# MCU.net
KiCad netlist of a schematic drawn in Altium Designer
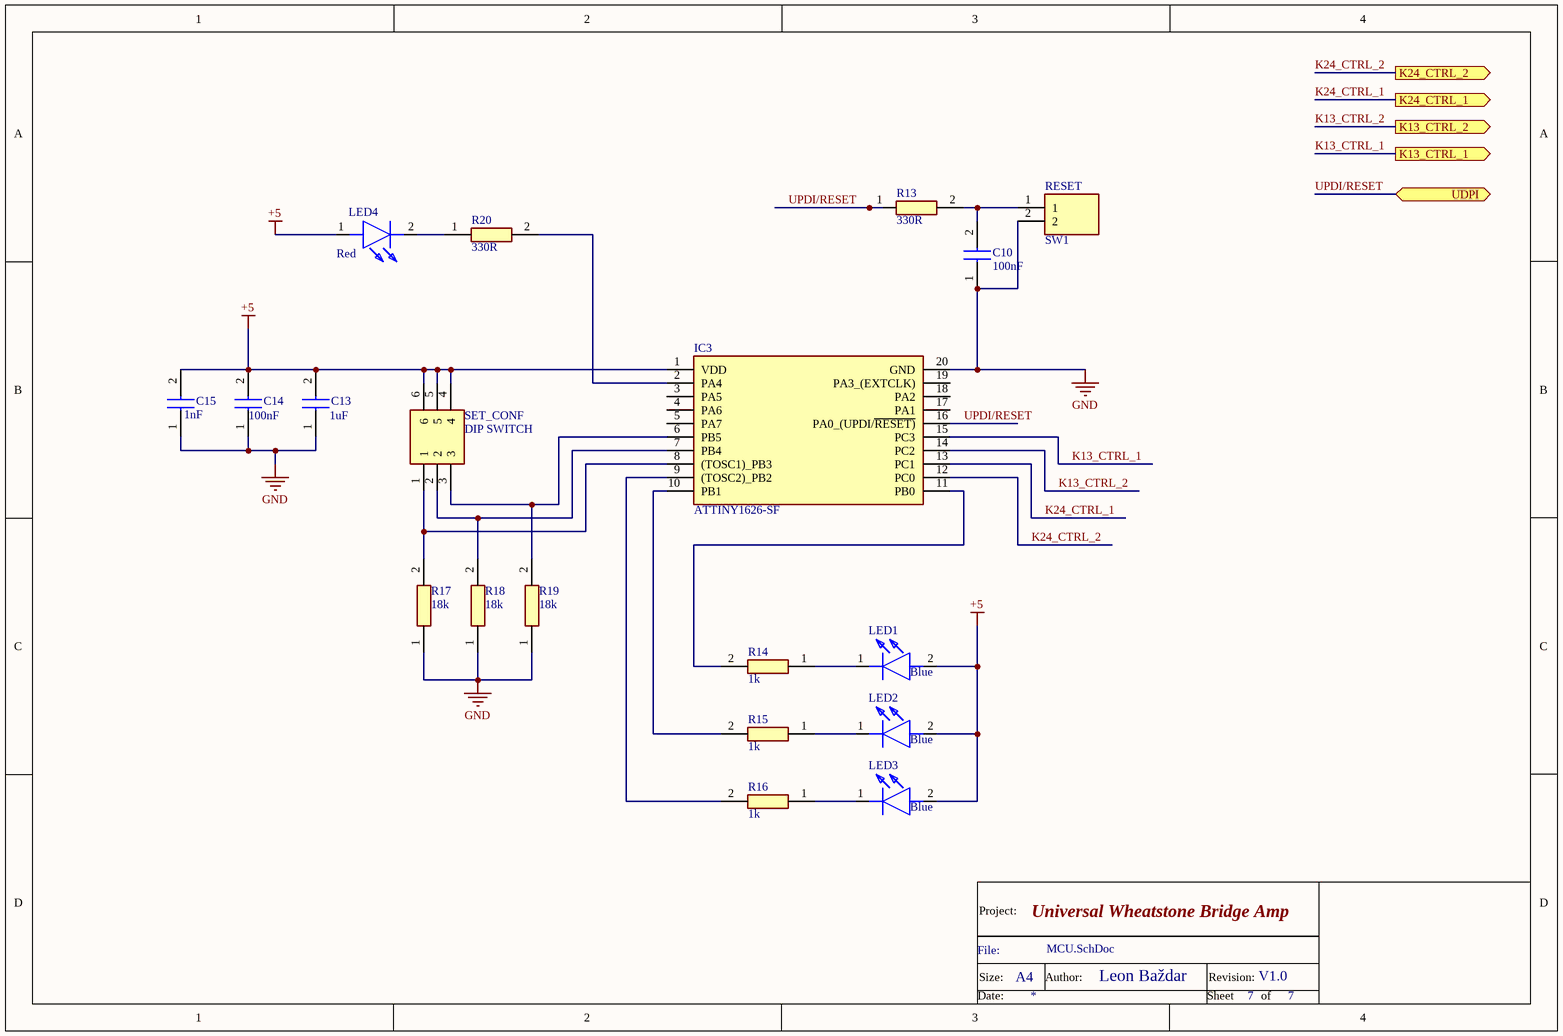
[diagram p0: MCU.SchDoc]

(export (version "E")
  (design (tool "Eeschema 10.0.6"))
  (components
    (comp (ref "C10")
      (value "100nF")
      (footprint "SamacSys:CAPC1005X55N")
      (description "Capacitor")
      (fields (field (name "MANUFACTURER_PART_NUMBER") "GCM155L81E104KE02D"))
      (libsource (lib "*") (part "GCM155L81E104KE02D"))
    )
    (comp (ref "C13")
      (value "1uF")
      (footprint "SamacSys:CAPC1005X55N")
      (description "Capacitor")
      (fields (field (name "MANUFACTURER_PART_NUMBER") "GRT155C81E105KE13D"))
      (libsource (lib "*") (part "GRT155C81E105KE13D"))
    )
    (comp (ref "C14")
      (value "100nF")
      (footprint "SamacSys:CAPC1005X55N")
      (description "Capacitor")
      (fields (field (name "MANUFACTURER_PART_NUMBER") "GCM155L81E104KE02D"))
      (libsource (lib "*") (part "GCM155L81E104KE02D"))
    )
    (comp (ref "C15")
      (value "1nF")
      (footprint "SamacSys:CAPC1005X55N")
      (description "Capacitor")
      (fields (field (name "MANUFACTURER_PART_NUMBER") "CGA2B2C0G1H102J050BE"))
      (libsource (lib "*") (part "CGA2B2C0G1H102J050BE"))
    )
    (comp (ref "IC3")
      (value "ATTINY1626-SF")
      (footprint "SamacSys:SOIC127P1030X265-20N")
      (description "Integrated Circuit")
      (libsource (lib "*") (part "ATTINY1626-SF"))
    )
    (comp (ref "LED1")
      (value "Blue")
      (footprint "SamacSys:LEDC2012X85N")
      (description "LED")
      (fields
        (field (name "MOUSER2 PART NUMBER") "604-APT2012LVBCD")
        (field (name "MANUFACTURER_PART_NUMBER") "APT2012LVBC/D")
      )
      (libsource (lib "*") (part "APT2012LVBC_D"))
    )
    (comp (ref "LED2")
      (value "Blue")
      (footprint "SamacSys:LEDC2012X85N")
      (description "LED")
      (fields
        (field (name "MOUSER2 PART NUMBER") "604-APT2012LVBCD")
        (field (name "MANUFACTURER_PART_NUMBER") "APT2012LVBC/D")
      )
      (libsource (lib "*") (part "APT2012LVBC_D"))
    )
    (comp (ref "LED3")
      (value "Blue")
      (footprint "SamacSys:LEDC2012X85N")
      (description "LED")
      (fields
        (field (name "MOUSER2 PART NUMBER") "604-APT2012LVBCD")
        (field (name "MANUFACTURER_PART_NUMBER") "APT2012LVBC/D")
      )
      (libsource (lib "*") (part "APT2012LVBC_D"))
    )
    (comp (ref "LED4")
      (value "Red")
      (footprint "SamacSys:APT2012SECKJ3PRV")
      (description "LED")
      (fields (field (name "MANUFACTURER_PART_NUMBER") "APT2012SECK/J3-PRV"))
      (libsource (lib "*") (part "APT2012SECK_J3-PRV"))
    )
    (comp (ref "R13")
      (value "330R")
      (footprint "SamacSys:ERJ2RKD1004X")
      (description "Resistor")
      (fields (field (name "MANUFACTURER_PART_NUMBER") "ERJ-2RHD3300X"))
      (libsource (lib "*") (part "ERJ-2RHD3300X"))
    )
    (comp (ref "R14")
      (value "1k")
      (footprint "SamacSys:ERA2V_(0402)")
      (description "Resistor")
      (fields (field (name "MANUFACTURER_PART_NUMBER") "ERA-2VEB1001X"))
      (libsource (lib "*") (part "ERA-2VEB1001X"))
    )
    (comp (ref "R15")
      (value "1k")
      (footprint "SamacSys:ERA2V_(0402)")
      (description "Resistor")
      (fields (field (name "MANUFACTURER_PART_NUMBER") "ERA-2VEB1001X"))
      (libsource (lib "*") (part "ERA-2VEB1001X"))
    )
    (comp (ref "R16")
      (value "1k")
      (footprint "SamacSys:ERA2V_(0402)")
      (description "Resistor")
      (fields (field (name "MANUFACTURER_PART_NUMBER") "ERA-2VEB1001X"))
      (libsource (lib "*") (part "ERA-2VEB1001X"))
    )
    (comp (ref "R17")
      (value "18k")
      (footprint "SamacSys:RESC1005X35N")
      (description "Resistor")
      (fields (field (name "MANUFACTURER_PART_NUMBER") "CPF0402B18KE1"))
      (libsource (lib "*") (part "CPF0402B18KE1"))
    )
    (comp (ref "R18")
      (value "18k")
      (footprint "SamacSys:RESC1005X35N")
      (description "Resistor")
      (fields (field (name "MANUFACTURER_PART_NUMBER") "CPF0402B18KE1"))
      (libsource (lib "*") (part "CPF0402B18KE1"))
    )
    (comp (ref "R19")
      (value "18k")
      (footprint "SamacSys:RESC1005X35N")
      (description "Resistor")
      (fields (field (name "MANUFACTURER_PART_NUMBER") "CPF0402B18KE1"))
      (libsource (lib "*") (part "CPF0402B18KE1"))
    )
    (comp (ref "R20")
      (value "330R")
      (footprint "SamacSys:ERJ2RKD1004X")
      (description "Resistor")
      (fields (field (name "MANUFACTURER_PART_NUMBER") "ERJ-2RHD3300X"))
      (libsource (lib "*") (part "ERJ-2RHD3300X"))
    )
    (comp (ref "RESET")
      (value "SW1")
      (footprint "SamacSys:95C04A3GWRT")
      (description "Switch")
      (fields
        (field (name "MOUSER2 PART NUMBER") "706-95C04A3GWRT")
        (field (name "MANUFACTURER_PART_NUMBER") "95C04A3GWRT")
      )
      (libsource (lib "*") (part "95C04A3GWRT"))
    )
    (comp (ref "SET_CONF")
      (value "DIP SWITCH")
      (footprint "SamacSys:2193LPSTR")
      (description "Switch")
      (fields (field (name "MANUFACTURER_PART_NUMBER") "219-3LPSTR"))
      (libsource (lib "*") (part "219-3LPSTR"))
    )
  )
  (nets
    (net (code "1") (name "+5") (class "Default")
      (node (ref "C13") (pin "2") (pinfunction "2_2") (pintype "passive"))
      (node (ref "C14") (pin "2") (pinfunction "2_2") (pintype "passive"))
      (node (ref "C15") (pin "2") (pinfunction "2_2") (pintype "passive"))
      (node (ref "IC3") (pin "1") (pinfunction "VDD_1") (pintype "passive"))
      (node (ref "LED1") (pin "2") (pinfunction "A_2") (pintype "passive"))
      (node (ref "LED2") (pin "2") (pinfunction "A_2") (pintype "passive"))
      (node (ref "LED3") (pin "2") (pinfunction "A_2") (pintype "passive"))
      (node (ref "LED4") (pin "1") (pinfunction "A_1") (pintype "passive"))
      (node (ref "SET_CONF") (pin "4") (pinfunction "4_4") (pintype "passive"))
      (node (ref "SET_CONF") (pin "5") (pinfunction "5_5") (pintype "passive"))
      (node (ref "SET_CONF") (pin "6") (pinfunction "6_6") (pintype "passive"))
    )
    (net (code "2") (name "/K13_CTRL_1") (class "Default")
      (node (ref "IC3") (pin "15") (pinfunction "PC3_15") (pintype "passive"))
    )
    (net (code "3") (name "/K13_CTRL_2") (class "Default")
      (node (ref "IC3") (pin "14") (pinfunction "PC2_14") (pintype "passive"))
    )
    (net (code "4") (name "/K24_CTRL_1") (class "Default")
      (node (ref "IC3") (pin "13") (pinfunction "PC1_13") (pintype "passive"))
    )
    (net (code "5") (name "/K24_CTRL_2") (class "Default")
      (node (ref "IC3") (pin "12") (pinfunction "PC0_12") (pintype "passive"))
    )
    (net (code "6") (name "/UPDI{slash}RESET") (class "Default")
      (node (ref "IC3") (pin "16") (pinfunction "PA0_(UPDI/~{RESET)}_16") (pintype "passive"))
      (node (ref "R13") (pin "1") (pinfunction "1_1") (pintype "passive"))
    )
    (net (code "7") (name "GND") (class "Default")
      (node (ref "C10") (pin "1") (pinfunction "1_1") (pintype "passive"))
      (node (ref "C13") (pin "1") (pinfunction "1_1") (pintype "passive"))
      (node (ref "C14") (pin "1") (pinfunction "1_1") (pintype "passive"))
      (node (ref "C15") (pin "1") (pinfunction "1_1") (pintype "passive"))
      (node (ref "IC3") (pin "20") (pinfunction "GND_20") (pintype "passive"))
      (node (ref "R17") (pin "1") (pinfunction "1_1") (pintype "passive"))
      (node (ref "R18") (pin "1") (pinfunction "1_1") (pintype "passive"))
      (node (ref "R19") (pin "1") (pinfunction "1_1") (pintype "passive"))
      (node (ref "RESET") (pin "2") (pinfunction "2_2") (pintype "passive"))
    )
    (net (code "8") (name "Net-(C10-Pad2)") (class "Default")
      (node (ref "C10") (pin "2") (pinfunction "2_2") (pintype "passive"))
      (node (ref "R13") (pin "2") (pinfunction "2_2") (pintype "passive"))
      (node (ref "RESET") (pin "1") (pinfunction "1_1") (pintype "passive"))
    )
    (net (code "9") (name "Net-(IC3-(TOSC1)_PB3)") (class "Default")
      (node (ref "IC3") (pin "8") (pinfunction "(TOSC1)_PB3_8") (pintype "passive"))
      (node (ref "R17") (pin "2") (pinfunction "2_2") (pintype "passive"))
      (node (ref "SET_CONF") (pin "1") (pinfunction "1_1") (pintype "passive"))
    )
    (net (code "10") (name "Net-(IC3-(TOSC2)_PB2)") (class "Default")
      (node (ref "IC3") (pin "9") (pinfunction "(TOSC2)_PB2_9") (pintype "passive"))
      (node (ref "R16") (pin "2") (pinfunction "2_2") (pintype "passive"))
    )
    (net (code "11") (name "Net-(IC3-PA4)") (class "Default")
      (node (ref "IC3") (pin "2") (pinfunction "PA4_2") (pintype "passive"))
      (node (ref "R20") (pin "2") (pinfunction "2_2") (pintype "passive"))
    )
    (net (code "12") (name "Net-(IC3-PB0)") (class "Default")
      (node (ref "IC3") (pin "11") (pinfunction "PB0_11") (pintype "passive"))
      (node (ref "R14") (pin "2") (pinfunction "2_2") (pintype "passive"))
    )
    (net (code "13") (name "Net-(IC3-PB1)") (class "Default")
      (node (ref "IC3") (pin "10") (pinfunction "PB1_10") (pintype "passive"))
      (node (ref "R15") (pin "2") (pinfunction "2_2") (pintype "passive"))
    )
    (net (code "14") (name "Net-(IC3-PB4)") (class "Default")
      (node (ref "IC3") (pin "7") (pinfunction "PB4_7") (pintype "passive"))
      (node (ref "R18") (pin "2") (pinfunction "2_2") (pintype "passive"))
      (node (ref "SET_CONF") (pin "2") (pinfunction "2_2") (pintype "passive"))
    )
    (net (code "15") (name "Net-(IC3-PB5)") (class "Default")
      (node (ref "IC3") (pin "6") (pinfunction "PB5_6") (pintype "passive"))
      (node (ref "R19") (pin "2") (pinfunction "2_2") (pintype "passive"))
      (node (ref "SET_CONF") (pin "3") (pinfunction "3_3") (pintype "passive"))
    )
    (net (code "16") (name "Net-(LED1-K)") (class "Default")
      (node (ref "LED1") (pin "1") (pinfunction "K_1") (pintype "passive"))
      (node (ref "R14") (pin "1") (pinfunction "1_1") (pintype "passive"))
    )
    (net (code "17") (name "Net-(LED2-K)") (class "Default")
      (node (ref "LED2") (pin "1") (pinfunction "K_1") (pintype "passive"))
      (node (ref "R15") (pin "1") (pinfunction "1_1") (pintype "passive"))
    )
    (net (code "18") (name "Net-(LED3-K)") (class "Default")
      (node (ref "LED3") (pin "1") (pinfunction "K_1") (pintype "passive"))
      (node (ref "R16") (pin "1") (pinfunction "1_1") (pintype "passive"))
    )
    (net (code "19") (name "Net-(LED4-K)") (class "Default")
      (node (ref "LED4") (pin "2") (pinfunction "K_2") (pintype "passive"))
      (node (ref "R20") (pin "1") (pinfunction "1_1") (pintype "passive"))
    )
    (net (code "20") (name "unconnected-(IC3-PA1-Pad17)") (class "Default")
      (node (ref "IC3") (pin "17") (pinfunction "PA1_17") (pintype "passive"))
    )
    (net (code "21") (name "unconnected-(IC3-PA2-Pad18)") (class "Default")
      (node (ref "IC3") (pin "18") (pinfunction "PA2_18") (pintype "passive"))
    )
    (net (code "22") (name "unconnected-(IC3-PA3_(EXTCLK)-Pad19)") (class "Default")
      (node (ref "IC3") (pin "19") (pinfunction "PA3_(EXTCLK)_19") (pintype "passive"))
    )
    (net (code "23") (name "unconnected-(IC3-PA5-Pad3)") (class "Default")
      (node (ref "IC3") (pin "3") (pinfunction "PA5_3") (pintype "passive"))
    )
    (net (code "24") (name "unconnected-(IC3-PA6-Pad4)") (class "Default")
      (node (ref "IC3") (pin "4") (pinfunction "PA6_4") (pintype "passive"))
    )
    (net (code "25") (name "unconnected-(IC3-PA7-Pad5)") (class "Default")
      (node (ref "IC3") (pin "5") (pinfunction "PA7_5") (pintype "passive"))
    )
  )
)
